# qec_pcb_1.net
KiCad netlist of a schematic drawn in EAGLE
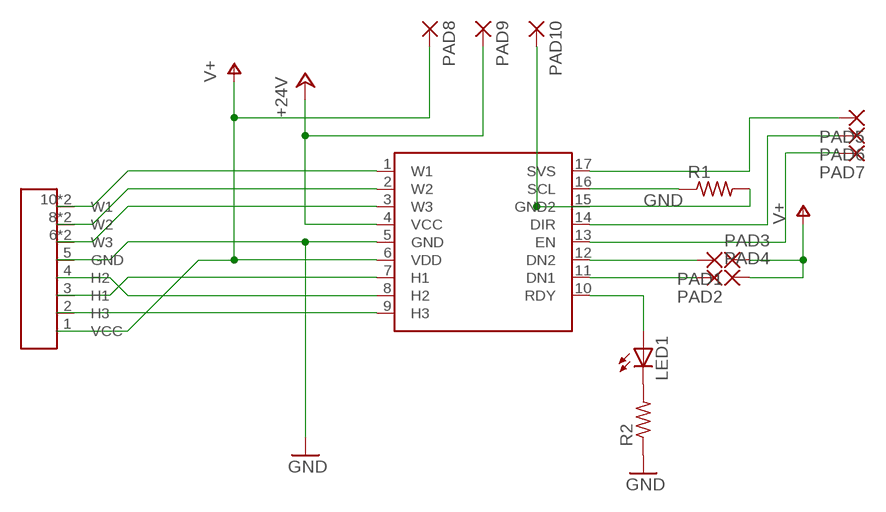
[diagram p0: schematic, sheet 1]

(export (version "E")
  (design (tool "Eeschema 10.0.6"))
  (components
    (comp (ref "K1")
      (value "68611114122")
      (footprint "eagle-import:68611114122")
      (libsource (lib "eagle-import") (part "68611114122"))
    )
    (comp (ref "LED1")
      (value "LEDCHIPLED_0805")
      (footprint "eagle-import:CHIPLED_0805")
      (libsource (lib "eagle-import") (part "LEDCHIPLED_0805"))
    )
    (comp (ref "PAD1")
      (value "SMD2")
      (footprint "eagle-import:SMD1,27-2,54")
      (libsource (lib "eagle-import") (part "SMD2"))
    )
    (comp (ref "PAD2")
      (value "SMD2")
      (footprint "eagle-import:SMD1,27-2,54")
      (libsource (lib "eagle-import") (part "SMD2"))
    )
    (comp (ref "PAD3")
      (value "SMD2")
      (footprint "eagle-import:SMD1,27-2,54")
      (libsource (lib "eagle-import") (part "SMD2"))
    )
    (comp (ref "PAD4")
      (value "SMD2")
      (footprint "eagle-import:SMD1,27-2,54")
      (libsource (lib "eagle-import") (part "SMD2"))
    )
    (comp (ref "PAD5")
      (value "SMD2")
      (footprint "eagle-import:SMD1,27-2,54")
      (libsource (lib "eagle-import") (part "SMD2"))
    )
    (comp (ref "PAD6")
      (value "SMD2")
      (footprint "eagle-import:SMD1,27-2,54")
      (libsource (lib "eagle-import") (part "SMD2"))
    )
    (comp (ref "PAD7")
      (value "SMD2")
      (footprint "eagle-import:SMD1,27-2,54")
      (libsource (lib "eagle-import") (part "SMD2"))
    )
    (comp (ref "PAD8")
      (value "SMD5")
      (footprint "eagle-import:SMD2,54-5,08")
      (libsource (lib "eagle-import") (part "SMD5"))
    )
    (comp (ref "PAD9")
      (value "SMD5")
      (footprint "eagle-import:SMD2,54-5,08")
      (libsource (lib "eagle-import") (part "SMD5"))
    )
    (comp (ref "PAD10")
      (value "SMD5")
      (footprint "eagle-import:SMD2,54-5,08")
      (libsource (lib "eagle-import") (part "SMD5"))
    )
    (comp (ref "R1")
      (value "R-US_M0805")
      (footprint "eagle-import:M0805")
      (libsource (lib "eagle-import") (part "R-US_M0805"))
    )
    (comp (ref "R2")
      (value "R-US_M0805")
      (footprint "eagle-import:M0805")
      (libsource (lib "eagle-import") (part "R-US_M0805"))
    )
    (comp (ref "U$1")
      (value "1-Q-EC1-Q-EC-SMD")
      (footprint "eagle-import:1-Q-EC-SMD")
      (libsource (lib "eagle-import") (part "1-Q-EC1-Q-EC-SMD"))
    )
  )
  (nets
    (net (code "1") (name "+24V") (class "Default")
      (node (ref "PAD9") (pin "1") (pinfunction "P_1") (pintype "passive"))
      (node (ref "U$1") (pin "4") (pinfunction "VCC_4") (pintype "bidirectional"))
    )
    (net (code "2") (name "GND") (class "Default")
      (node (ref "K1") (pin "5") (pinfunction "GND_5") (pintype "bidirectional"))
      (node (ref "PAD10") (pin "1") (pinfunction "P_1") (pintype "passive"))
      (node (ref "R1") (pin "2") (pinfunction "2_2") (pintype "passive"))
      (node (ref "R2") (pin "1") (pinfunction "1_1") (pintype "passive"))
      (node (ref "U$1") (pin "15") (pinfunction "GND2_15") (pintype "bidirectional"))
      (node (ref "U$1") (pin "5") (pinfunction "GND_5") (pintype "bidirectional"))
    )
    (net (code "3") (name "Net-(K1-H1)") (class "Default")
      (node (ref "K1") (pin "3") (pinfunction "H1_3") (pintype "bidirectional"))
      (node (ref "U$1") (pin "7") (pinfunction "H1_7") (pintype "bidirectional"))
    )
    (net (code "4") (name "Net-(K1-H2)") (class "Default")
      (node (ref "K1") (pin "4") (pinfunction "H2_4") (pintype "bidirectional"))
      (node (ref "U$1") (pin "8") (pinfunction "H2_8") (pintype "bidirectional"))
    )
    (net (code "5") (name "Net-(K1-H3)") (class "Default")
      (node (ref "K1") (pin "2") (pinfunction "H3_2") (pintype "bidirectional"))
      (node (ref "U$1") (pin "9") (pinfunction "H3_9") (pintype "bidirectional"))
    )
    (net (code "6") (name "Net-(LED1-PadC)") (class "Default")
      (node (ref "LED1") (pin "C") (pinfunction "C_C") (pintype "passive"))
      (node (ref "R2") (pin "2") (pinfunction "2_2") (pintype "passive"))
    )
    (net (code "7") (name "Net-(PAD1-P)") (class "Default")
      (node (ref "PAD1") (pin "1") (pinfunction "P_1") (pintype "passive"))
      (node (ref "U$1") (pin "12") (pinfunction "DN2_12") (pintype "bidirectional"))
    )
    (net (code "8") (name "Net-(PAD2-P)") (class "Default")
      (node (ref "PAD2") (pin "1") (pinfunction "P_1") (pintype "passive"))
      (node (ref "U$1") (pin "11") (pinfunction "DN1_11") (pintype "bidirectional"))
    )
    (net (code "9") (name "Net-(PAD5-P)") (class "Default")
      (node (ref "PAD5") (pin "1") (pinfunction "P_1") (pintype "passive"))
      (node (ref "U$1") (pin "17") (pinfunction "SVS_17") (pintype "bidirectional"))
    )
    (net (code "10") (name "Net-(PAD6-P)") (class "Default")
      (node (ref "PAD6") (pin "1") (pinfunction "P_1") (pintype "passive"))
      (node (ref "U$1") (pin "14") (pinfunction "DIR_14") (pintype "bidirectional"))
    )
    (net (code "11") (name "Net-(PAD7-P)") (class "Default")
      (node (ref "PAD7") (pin "1") (pinfunction "P_1") (pintype "passive"))
      (node (ref "U$1") (pin "13") (pinfunction "EN_13") (pintype "bidirectional"))
    )
    (net (code "12") (name "Net-(U$1-RDY)") (class "Default")
      (node (ref "LED1") (pin "A") (pinfunction "A_A") (pintype "passive"))
      (node (ref "U$1") (pin "10") (pinfunction "RDY_10") (pintype "bidirectional"))
    )
    (net (code "13") (name "Net-(U$1-SCL)") (class "Default")
      (node (ref "R1") (pin "1") (pinfunction "1_1") (pintype "passive"))
      (node (ref "U$1") (pin "16") (pinfunction "SCL_16") (pintype "bidirectional"))
    )
    (net (code "14") (name "Net-(U$1-W1)") (class "Default")
      (node (ref "K1") (pin "10") (pinfunction "W1_10") (pintype "bidirectional"))
      (node (ref "K1") (pin "11") (pinfunction "W1_11") (pintype "bidirectional"))
      (node (ref "U$1") (pin "1") (pinfunction "W1_1") (pintype "bidirectional"))
    )
    (net (code "15") (name "Net-(U$1-W2)") (class "Default")
      (node (ref "K1") (pin "8") (pinfunction "W2_8") (pintype "bidirectional"))
      (node (ref "K1") (pin "9") (pinfunction "W2_9") (pintype "bidirectional"))
      (node (ref "U$1") (pin "2") (pinfunction "W2_2") (pintype "bidirectional"))
    )
    (net (code "16") (name "Net-(U$1-W3)") (class "Default")
      (node (ref "K1") (pin "6") (pinfunction "W3_6") (pintype "bidirectional"))
      (node (ref "K1") (pin "7") (pinfunction "W3_7") (pintype "bidirectional"))
      (node (ref "U$1") (pin "3") (pinfunction "W3_3") (pintype "bidirectional"))
    )
    (net (code "17") (name "V+") (class "Default")
      (node (ref "K1") (pin "1") (pinfunction "VCC_1") (pintype "bidirectional"))
      (node (ref "PAD3") (pin "1") (pinfunction "P_1") (pintype "passive"))
      (node (ref "PAD4") (pin "1") (pinfunction "P_1") (pintype "passive"))
      (node (ref "PAD8") (pin "1") (pinfunction "P_1") (pintype "passive"))
      (node (ref "U$1") (pin "6") (pinfunction "VDD_6") (pintype "bidirectional"))
    )
  )
)
